# LM25148_eval_BRD.net
KiCad netlist of a schematic drawn in Altium Designer
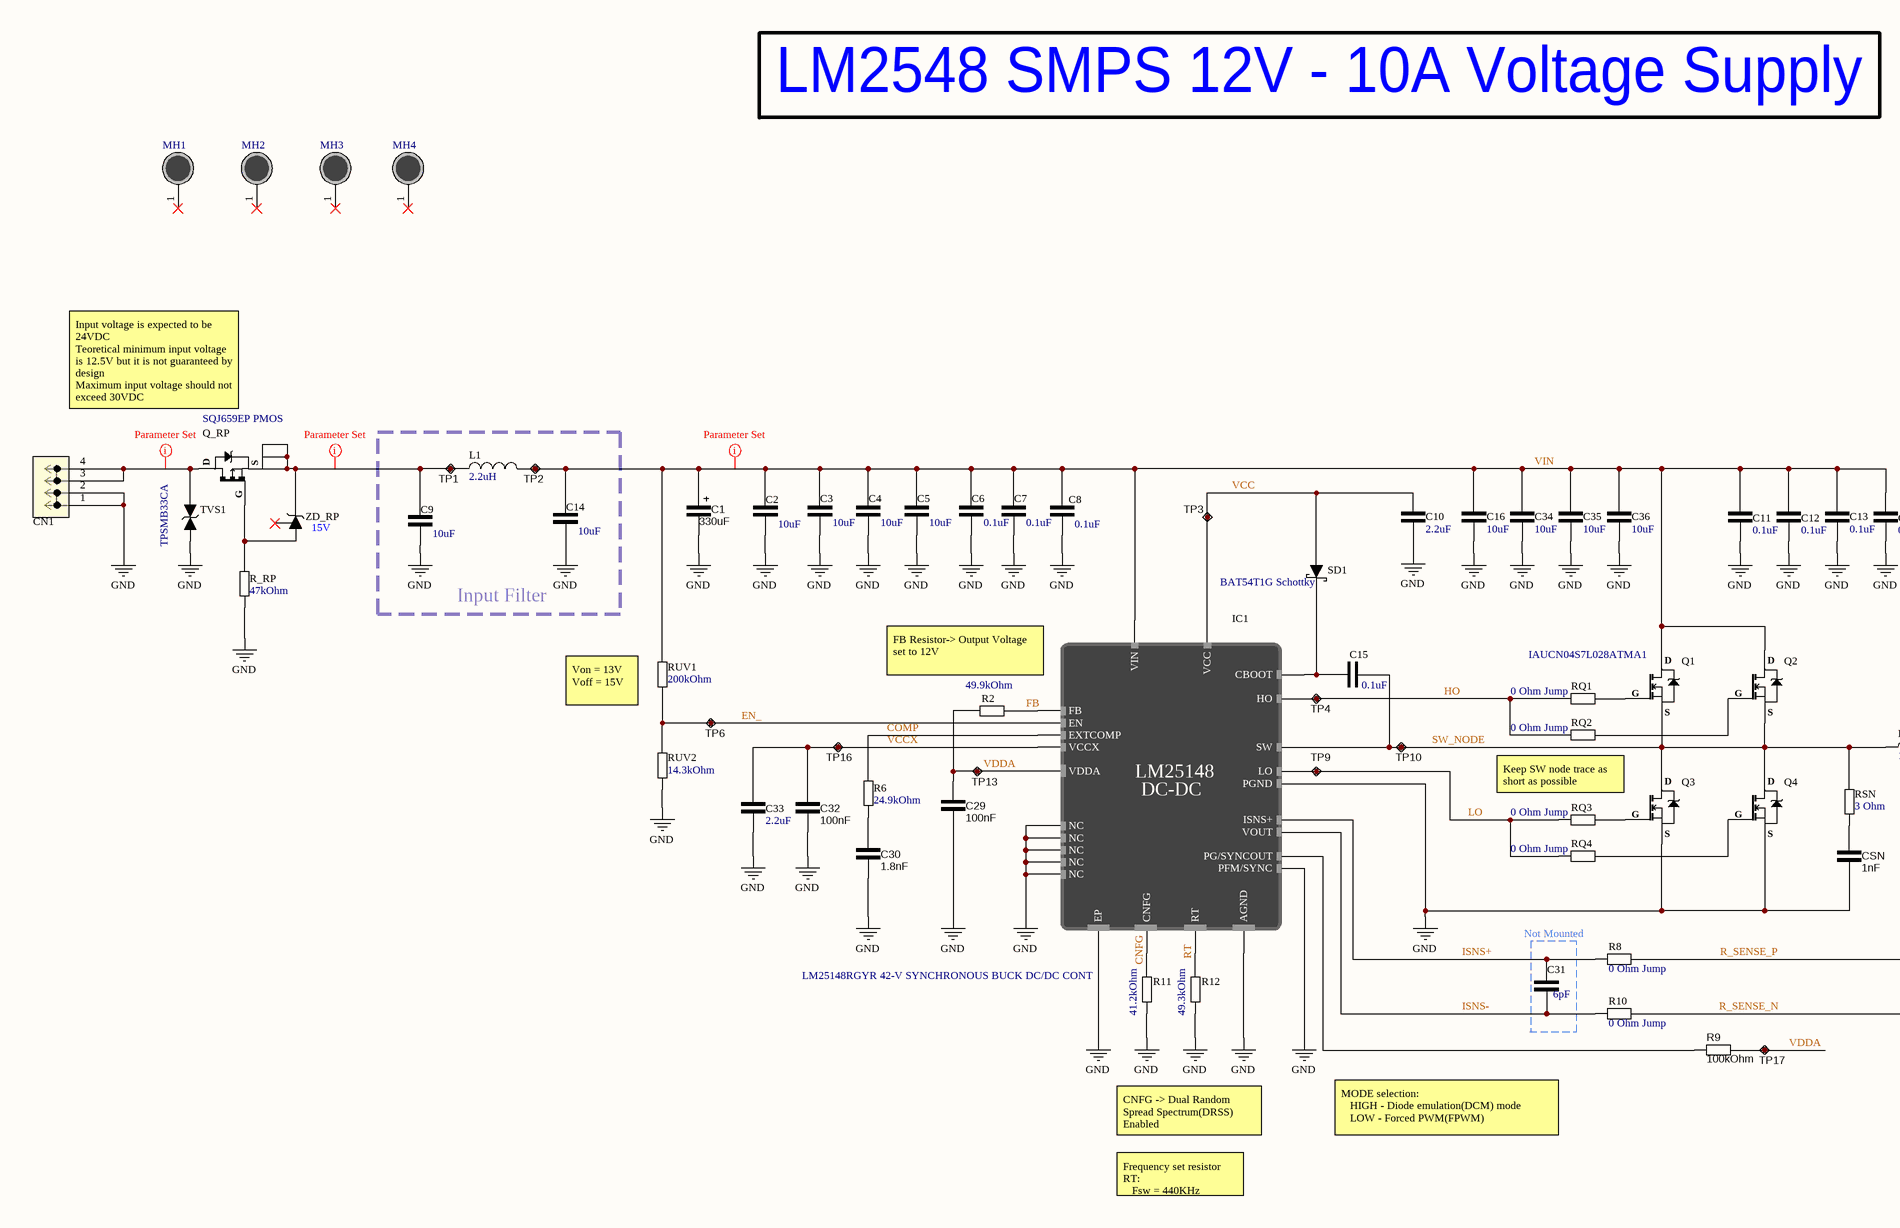
[diagram p0: LM25148_eval_BRD.SchDoc, left]
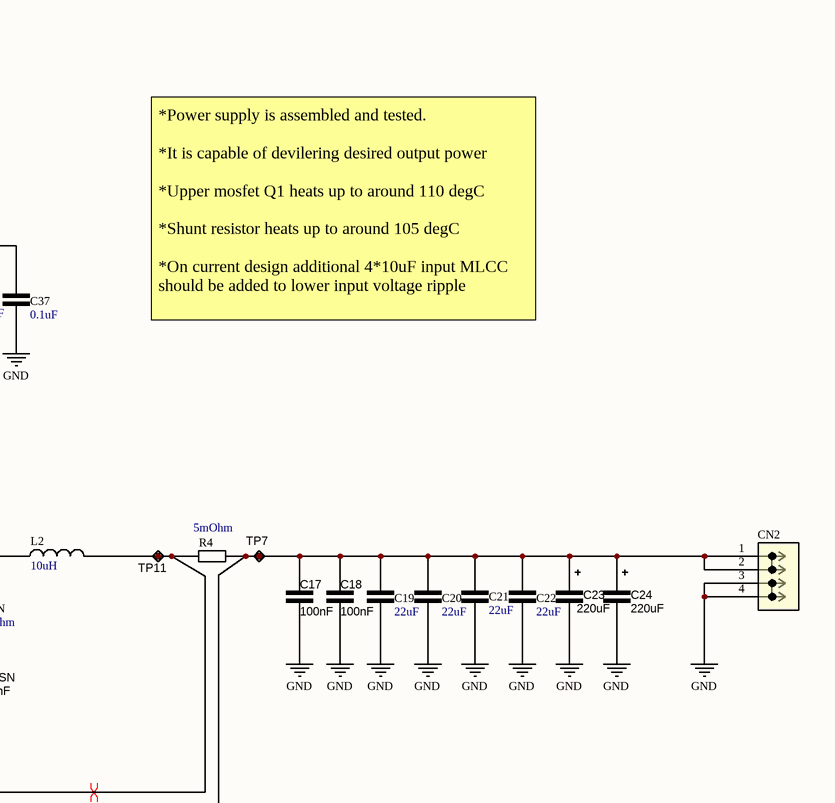
[diagram p1: LM25148_eval_BRD.SchDoc, right]

(export (version "E")
  (design (tool "Eeschema 10.0.6"))
  (components
    (comp (ref "C1")
      (value "330uF")
      (footprint "CAPAE109103X103M")
      (description "330 µF 50 V Aluminum Electrolytic Capacitors Radial, Can - SMD 120mOhm @ 100kHz 2000 Hrs @ 105°C")
      (fields (field (name "DIGIKEY PART NUMBER") "565-EMZR500ARA331MJA0GCT-ND"))
      (libsource (lib "CapacitorsIntegrated") (part "C000026"))
    )
    (comp (ref "C2")
      (value "10uF")
      (footprint "CAP_1206")
      (description "10 µF ±10% 50V Ceramic Capacitor X7R 1206 (3216 Metric)")
      (fields (field (name "DIGIKEY PART NUMBER") "1276-6767-1-ND"))
      (libsource (lib "CapacitorsIntegrated") (part "C000017"))
    )
    (comp (ref "C3")
      (value "10uF")
      (footprint "CAP_1206")
      (description "10 µF ±10% 50V Ceramic Capacitor X7R 1206 (3216 Metric)")
      (fields (field (name "DIGIKEY PART NUMBER") "1276-6767-1-ND"))
      (libsource (lib "") (part "C000017_1"))
    )
    (comp (ref "C4")
      (value "10uF")
      (footprint "CAP_1206")
      (description "10 µF ±10% 50V Ceramic Capacitor X7R 1206 (3216 Metric)")
      (fields (field (name "DIGIKEY PART NUMBER") "1276-6767-1-ND"))
      (libsource (lib "") (part "C000017_1"))
    )
    (comp (ref "C5")
      (value "10uF")
      (footprint "CAP_1206")
      (description "10 µF ±10% 50V Ceramic Capacitor X7R 1206 (3216 Metric)")
      (fields (field (name "DIGIKEY PART NUMBER") "1276-6767-1-ND"))
      (libsource (lib "") (part "C000017_1"))
    )
    (comp (ref "C6")
      (value "0.1uF")
      (footprint "CAP_0603")
      (description "0.1 µF ±10% 50V Ceramic Capacitor X7R 0603 (1608 Metric)")
      (fields (field (name "DIGIKEY PART NUMBER") "1276-1000-1-ND"))
      (libsource (lib "") (part "C000018_1"))
    )
    (comp (ref "C7")
      (value "0.1uF")
      (footprint "CAP_0603")
      (description "0.1 µF ±10% 50V Ceramic Capacitor X7R 0603 (1608 Metric)")
      (fields (field (name "DIGIKEY PART NUMBER") "1276-1000-1-ND"))
      (libsource (lib "") (part "C000018_1"))
    )
    (comp (ref "C8")
      (value "0.1uF")
      (footprint "CAP_0603")
      (description "0.1 µF ±10% 50V Ceramic Capacitor X7R 0603 (1608 Metric)")
      (fields (field (name "DIGIKEY PART NUMBER") "1276-1000-1-ND"))
      (libsource (lib "CapacitorsIntegrated") (part "C000018"))
    )
    (comp (ref "C9")
      (value "10uF")
      (footprint "CAP_1206")
      (description "10 µF ±10% 50V Ceramic Capacitor X7R 1206 (3216 Metric)")
      (fields (field (name "DIGIKEY PART NUMBER") "1276-6767-1-ND"))
      (libsource (lib "CapacitorsIntegrated") (part "C000017"))
    )
    (comp (ref "C10")
      (value "2.2uF")
      (footprint "CAP_0603")
      (description "8 pF ±0.05pF 25V Ceramic Capacitor C0G, NP0 01005 (0402 Metric)")
      (fields (field (name "DIGIKEY PART NUMBER") "490-12731-1-ND"))
      (libsource (lib "") (part "C000014_1"))
    )
    (comp (ref "C11")
      (value "0.1uF")
      (footprint "CAP_0603")
      (description "0.1 µF ±10% 50V Ceramic Capacitor X7R 0603 (1608 Metric)")
      (fields (field (name "DIGIKEY PART NUMBER") "1276-1000-1-ND"))
      (libsource (lib "CapacitorsIntegrated") (part "C000018"))
    )
    (comp (ref "C12")
      (value "0.1uF")
      (footprint "CAP_0603")
      (description "0.1 µF ±10% 50V Ceramic Capacitor X7R 0603 (1608 Metric)")
      (fields (field (name "DIGIKEY PART NUMBER") "1276-1000-1-ND"))
      (libsource (lib "CapacitorsIntegrated") (part "C000018"))
    )
    (comp (ref "C13")
      (value "0.1uF")
      (footprint "CAP_0603")
      (description "0.1 µF ±10% 50V Ceramic Capacitor X7R 0603 (1608 Metric)")
      (fields (field (name "DIGIKEY PART NUMBER") "1276-1000-1-ND"))
      (libsource (lib "") (part "C000018_1"))
    )
    (comp (ref "C14")
      (value "10uF")
      (footprint "CAP_1206")
      (description "10 µF ±10% 50V Ceramic Capacitor X7R 1206 (3216 Metric)")
      (fields (field (name "DIGIKEY PART NUMBER") "1276-6767-1-ND"))
      (libsource (lib "CapacitorsIntegrated") (part "C000017"))
    )
    (comp (ref "C15")
      (value "0.1uF")
      (footprint "CAP_0603")
      (description "0.1 µF ±10% 50V Ceramic Capacitor X7R 0603 (1608 Metric)")
      (fields (field (name "DIGIKEY PART NUMBER") "1276-1000-1-ND"))
      (libsource (lib "") (part "C000018_2"))
    )
    (comp (ref "C16")
      (value "10uF")
      (footprint "CAP_1206")
      (description "10 µF ±10% 50V Ceramic Capacitor X7R 1206 (3216 Metric)")
      (fields (field (name "DIGIKEY PART NUMBER") "1276-6767-1-ND"))
      (libsource (lib "") (part "C000017_1"))
    )
    (comp (ref "C17")
      (value "100nF")
      (footprint "CAP_0603")
      (description "0.1 µF ±10% 25V Ceramic Capacitor X7R 0603 (1608 Metric)")
      (fields (field (name "DIGIKEY PART NUMBER") "478-KAM15AR71E104KTCT-ND"))
      (libsource (lib "CapacitorsIntegrated") (part "C000007"))
    )
    (comp (ref "C18")
      (value "100nF")
      (footprint "CAP_0603")
      (description "0.1 µF ±10% 25V Ceramic Capacitor X7R 0603 (1608 Metric)")
      (fields (field (name "DIGIKEY PART NUMBER") "478-KAM15AR71E104KTCT-ND"))
      (libsource (lib "CapacitorsIntegrated") (part "C000007"))
    )
    (comp (ref "C19")
      (value "22uF")
      (footprint "CAP_1210")
      (description "22 µF ±10% 25V Ceramic Capacitor X7R 1210 (3225 Metric)")
      (fields (field (name "DIGIKEY PART NUMBER") "1276-3392-1-ND"))
      (libsource (lib "") (part "C000032_1"))
    )
    (comp (ref "C20")
      (value "22uF")
      (footprint "CAP_1210")
      (description "22 µF ±10% 25V Ceramic Capacitor X7R 1210 (3225 Metric)")
      (fields (field (name "DIGIKEY PART NUMBER") "1276-3392-1-ND"))
      (libsource (lib "") (part "C000032_1"))
    )
    (comp (ref "C21")
      (value "22uF")
      (footprint "CAP_1210")
      (description "22 µF ±10% 25V Ceramic Capacitor X7R 1210 (3225 Metric)")
      (fields (field (name "DIGIKEY PART NUMBER") "1276-3392-1-ND"))
      (libsource (lib "CapacitorsIntegrated") (part "C000032"))
    )
    (comp (ref "C22")
      (value "22uF")
      (footprint "CAP_1210")
      (description "22 µF ±10% 25V Ceramic Capacitor X7R 1210 (3225 Metric)")
      (fields (field (name "DIGIKEY PART NUMBER") "1276-3392-1-ND"))
      (libsource (lib "") (part "C000032_1"))
    )
    (comp (ref "C23")
      (value "220uF")
      (footprint "CAPAE109103X103M")
      (description "220 µF 35 V Aluminum - Polymer Capacitors Radial, Can - SMD 23mOhm 1000 Hrs @ 150°C")
      (fields (field (name "DIGIKEY PART NUMBER") "399-A785MN227M1VLAS023CT-ND"))
      (libsource (lib "CapacitorsIntegrated") (part "C000033"))
    )
    (comp (ref "C24")
      (value "220uF")
      (footprint "CAPAE109103X103M")
      (description "220 µF 35 V Aluminum - Polymer Capacitors Radial, Can - SMD 23mOhm 1000 Hrs @ 150°C")
      (fields (field (name "DIGIKEY PART NUMBER") "399-A785MN227M1VLAS023CT-ND"))
      (libsource (lib "CapacitorsIntegrated") (part "C000033"))
    )
    (comp (ref "C29")
      (value "100nF")
      (footprint "CAP_0603")
      (description "0.1 µF ±10% 25V Ceramic Capacitor X7R 0603 (1608 Metric)")
      (fields (field (name "DIGIKEY PART NUMBER") "478-KAM15AR71E104KTCT-ND"))
      (libsource (lib "CapacitorsIntegrated") (part "C000007"))
    )
    (comp (ref "C30")
      (value "1.8nF")
      (footprint "CAP_0603")
      (description "1800 pF ±10% 25V Ceramic Capacitor X7R 0603 (1608 Metric)")
      (fields (field (name "DIGIKEY PART NUMBER") "399-15370-1-ND"))
      (libsource (lib "CapacitorsIntegrated") (part "C000027"))
    )
    (comp (ref "C31")
      (value "6pF")
      (footprint "CAP_0402")
      (description "6 pF ±0.5pF 25V Ceramic Capacitor C0G, NP0 0402 (1005 Metric)")
      (fields (field (name "DIGIKEY PART NUMBER") "399-CBR04C609D3GACCT-ND"))
      (libsource (lib "CapacitorsIntegrated") (part "C000016"))
    )
    (comp (ref "C32")
      (value "100nF")
      (footprint "CAP_0603")
      (description "0.1 µF ±10% 25V Ceramic Capacitor X7R 0603 (1608 Metric)")
      (fields (field (name "DIGIKEY PART NUMBER") "478-KAM15AR71E104KTCT-ND"))
      (libsource (lib "CapacitorsIntegrated") (part "C000007"))
    )
    (comp (ref "C33")
      (value "2.2uF")
      (footprint "CAP_0603")
      (description "8 pF ±0.05pF 25V Ceramic Capacitor C0G, NP0 01005 (0402 Metric)")
      (fields (field (name "DIGIKEY PART NUMBER") "490-12731-1-ND"))
      (libsource (lib "CapacitorsIntegrated") (part "C000014"))
    )
    (comp (ref "C34")
      (value "10uF")
      (footprint "CAP_1206")
      (description "10 µF ±10% 50V Ceramic Capacitor X7R 1206 (3216 Metric)")
      (fields (field (name "DIGIKEY PART NUMBER") "1276-6767-1-ND"))
      (libsource (lib "") (part "C000017_1"))
    )
    (comp (ref "C35")
      (value "10uF")
      (footprint "CAP_1206")
      (description "10 µF ±10% 50V Ceramic Capacitor X7R 1206 (3216 Metric)")
      (fields (field (name "DIGIKEY PART NUMBER") "1276-6767-1-ND"))
      (libsource (lib "") (part "C000017_1"))
    )
    (comp (ref "C36")
      (value "10uF")
      (footprint "CAP_1206")
      (description "10 µF ±10% 50V Ceramic Capacitor X7R 1206 (3216 Metric)")
      (fields (field (name "DIGIKEY PART NUMBER") "1276-6767-1-ND"))
      (libsource (lib "") (part "C000017_1"))
    )
    (comp (ref "C37")
      (value "0.1uF")
      (footprint "CAP_0603")
      (description "0.1 µF ±10% 50V Ceramic Capacitor X7R 0603 (1608 Metric)")
      (fields (field (name "DIGIKEY PART NUMBER") "1276-1000-1-ND"))
      (libsource (lib "CapacitorsIntegrated") (part "C000018"))
    )
    (comp (ref "CN1")
      (value "TERM BLK PCB LEVER 3.5MM 2POS")
      (footprint "CONN2_2601-1102_WAG")
      (description "2 Position Wire to Board Terminal Block Horizontal with Board 0.138\" (3.50mm) Through Hole")
      (fields (field (name "DIGIKEY PART NUMBER") "2946-2601-1102-ND"))
      (libsource (lib "") (part "00000017_1"))
    )
    (comp (ref "CN2")
      (value "TERM BLK PCB LEVER 3.5MM 2POS")
      (footprint "CONN2_2601-1102_WAG")
      (description "2 Position Wire to Board Terminal Block Horizontal with Board 0.138\" (3.50mm) Through Hole")
      (fields (field (name "DIGIKEY PART NUMBER") "2946-2601-1102-ND"))
      (libsource (lib "ElectroMechanical") (part "00000017"))
    )
    (comp (ref "CSN")
      (value "1nF")
      (footprint "CAP_0805")
      (description "1000 pF ±10% 100V Ceramic Capacitor X7R 0805 (2012 Metric)")
      (fields (field (name "DIGIKEY PART NUMBER") "311-1472-1-ND"))
      (libsource (lib "CapacitorsIntegrated") (part "C000035"))
    )
    (comp (ref "IC1")
      (value "LM25148RGYR 42-V SYNCHRONOUS BUCK DC/DC CONT")
      (footprint "VQFN25_RGY_TEX")
      (description "Buck Regulator Positive Output Step-Down DC-DC Controller IC 24-VQFN (5.5x3.5)")
      (fields
        (field (name "DIGIKEY PART NUMBER") "296-LM25148RGYRCT-ND")
        (field (name "MOUSER PART NUMBER") "595-LM25148RGYR")
      )
      (libsource (lib "IntegratedCircuits") (part "LM25148RGYR"))
    )
    (comp (ref "L1")
      (value "2.2uH")
      (footprint "IHLP-3232DZ-51")
      (description "FIXED IND 2.2UH 11.5A 12.5 MOHM")
      (fields
        (field (name "DIGIKEY PART NUMBER") "541-IHLP3232DZER2R2M5ACT-ND")
        (field (name "MOUSER PART NUMBER") "70-IHLP3232DZR2R2M5A")
      )
      (libsource (lib "InductorIntegrated") (part "L000015"))
    )
    (comp (ref "L2")
      (value "10uH")
      (footprint "INDP135126X65N")
      (description "FIXED IND 10UH 11A 15.8 MOHM SMD")
      (fields
        (field (name "DIGIKEY PART NUMBER") "553-4029-1-ND")
        (field (name "MOUSER PART NUMBER") "673-PA4343.103ANLT")
      )
      (libsource (lib "InductorIntegrated") (part "L000016"))
    )
    (comp (ref "MH1")
      (value "Mounting Hole")
      (footprint "HOLE-3mm")
      (description "Mounting Hole 3mm")
      (libsource (lib "ElectroMechanical") (part "00000006"))
    )
    (comp (ref "MH2")
      (value "Mounting Hole")
      (footprint "HOLE-3mm")
      (description "Mounting Hole 3mm")
      (libsource (lib "ElectroMechanical") (part "00000006"))
    )
    (comp (ref "MH3")
      (value "Mounting Hole")
      (footprint "HOLE-3mm")
      (description "Mounting Hole 3mm")
      (libsource (lib "ElectroMechanical") (part "00000006"))
    )
    (comp (ref "MH4")
      (value "Mounting Hole")
      (footprint "HOLE-3mm")
      (description "Mounting Hole 3mm")
      (libsource (lib "ElectroMechanical") (part "00000006"))
    )
    (comp (ref "Q1")
      (value "IAUCN04S7L028ATMA1")
      (footprint "PG-TDSON-8-33")
      (description "N-Channel 40 V 100A Surface Mount PG-TDSON-8-33")
      (fields
        (field (name "DIGIKEY PART NUMBER") "448-IAUCN04S7L028ATMA1CT-ND")
        (field (name "MOUSER PART NUMBER") "726-IAUCN04S7L028ATM")
      )
      (libsource (lib "Miscellaneous_Lib1") (part "00000014"))
    )
    (comp (ref "Q2")
      (value "IAUCN04S7L028ATMA1")
      (footprint "PG-TDSON-8-33")
      (description "N-Channel 40 V 100A Surface Mount PG-TDSON-8-33")
      (fields
        (field (name "DIGIKEY PART NUMBER") "448-IAUCN04S7L028ATMA1CT-ND")
        (field (name "MOUSER PART NUMBER") "726-IAUCN04S7L028ATM")
      )
      (libsource (lib "Miscellaneous_Lib1") (part "00000014"))
    )
    (comp (ref "Q3")
      (value "IAUCN04S7L028ATMA1")
      (footprint "PG-TDSON-8-33")
      (description "N-Channel 40 V 100A Surface Mount PG-TDSON-8-33")
      (fields
        (field (name "DIGIKEY PART NUMBER") "448-IAUCN04S7L028ATMA1CT-ND")
        (field (name "MOUSER PART NUMBER") "726-IAUCN04S7L028ATM")
      )
      (libsource (lib "Miscellaneous_Lib1") (part "00000014"))
    )
    (comp (ref "Q4")
      (value "IAUCN04S7L028ATMA1")
      (footprint "PG-TDSON-8-33")
      (description "N-Channel 40 V 100A Surface Mount PG-TDSON-8-33")
      (fields
        (field (name "DIGIKEY PART NUMBER") "448-IAUCN04S7L028ATMA1CT-ND")
        (field (name "MOUSER PART NUMBER") "726-IAUCN04S7L028ATM")
      )
      (libsource (lib "Miscellaneous_Lib1") (part "00000014"))
    )
    (comp (ref "Q_RP")
      (value "SQJ659EP PMOS")
      (footprint "PowerPAK SO-8L SINGLE")
      (description "P-Channel 60 V 52A (Tc) 83W (Tc) Surface Mount PowerPAK® SO-8")
      (fields
        (field (name "DIGIKEY PART NUMBER") "SQJ459EP-T1_GE3CT-ND")
        (field (name "MOUSER PART NUMBER") "78-SQJ459EP-T2_BE3")
      )
      (libsource (lib "Miscellaneous_Lib1") (part "00000005"))
    )
    (comp (ref "R2")
      (value "49.9kOhm")
      (footprint "RES_0603")
      (description "49.9 kOhms ±1% 0.1W, 1/10W Chip Resistor 0603 (1608 Metric) Moisture Resistant Thick Film")
      (fields (field (name "DIGIKEY PART NUMBER") "541-49.9KHCT-ND"))
      (libsource (lib "ResistorsIntegrated") (part "R000025"))
    )
    (comp (ref "R4")
      (value "5mOhm")
      (footprint "SENSE_RES_2512")
      (fields (field (name "DIGIKEY PART NUMBER") "CRF2512-FZ-R005ELFCT-ND"))
      (libsource (lib "ResistorsIntegrated") (part "R000033"))
    )
    (comp (ref "R6")
      (value "24.9kOhm")
      (footprint "RES_0603")
      (description "24.9 kOhms ±1% 0.1W, 1/10W Chip Resistor 0603 (1608 Metric) Automotive AEC-Q200 Thick Film")
      (fields (field (name "DIGIKEY PART NUMBER") "P24.9KHCT-ND"))
      (libsource (lib "ResistorsIntegrated") (part "R000017"))
    )
    (comp (ref "R8")
      (value "0 Ohm Jump")
      (footprint "RES_0402")
      (description "0 Ohms Jumper Chip Resistor 0402 (1005 Metric) Automotive AEC-Q200 Thick Film")
      (fields (field (name "DIGIKEY PART NUMBER") "P0.0JCT-ND"))
      (libsource (lib "ResistorsIntegrated") (part "R000008"))
    )
    (comp (ref "R9")
      (value "100kOhm")
      (footprint "RES_0603")
      (description "100 kOhms ±1% 0.1W, 1/10W Chip Resistor 0603 (1608 Metric) Automotive AEC-Q200 Thick Film")
      (fields (field (name "DIGIKEY PART NUMBER") "RMCF0603FG100KCT-ND"))
      (libsource (lib "ResistorsIntegrated") (part "R000006"))
    )
    (comp (ref "R10")
      (value "0 Ohm Jump")
      (footprint "RES_0402")
      (description "0 Ohms Jumper Chip Resistor 0402 (1005 Metric) Automotive AEC-Q200 Thick Film")
      (fields (field (name "DIGIKEY PART NUMBER") "P0.0JCT-ND"))
      (libsource (lib "ResistorsIntegrated") (part "R000008"))
    )
    (comp (ref "R11")
      (value "41.2kOhm")
      (footprint "RES_0603")
      (description "41.2 kOhms ±1% 0.1W, 1/10W Chip Resistor 0603 (1608 Metric) Automotive AEC-Q200 Thick Film")
      (fields (field (name "DIGIKEY PART NUMBER") "P41.2KHCT-ND"))
      (libsource (lib "ResistorsIntegrated") (part "R000015"))
    )
    (comp (ref "R12")
      (value "49.3kOhm")
      (footprint "RES_0603")
      (description "49.3 kOhms ±0.1% 0.1W, 1/10W Chip Resistor 0603 (1608 Metric) Thin Film")
      (fields (field (name "DIGIKEY PART NUMBER") "13-RT0603BRD0749K3LCT-ND"))
      (libsource (lib "ResistorsIntegrated") (part "R000023"))
    )
    (comp (ref "RQ1")
      (value "0 Ohm Jump")
      (footprint "RES_0402")
      (description "0 Ohms Jumper Chip Resistor 0402 (1005 Metric) Automotive AEC-Q200 Thick Film")
      (fields (field (name "DIGIKEY PART NUMBER") "P0.0JCT-ND"))
      (libsource (lib "ResistorsIntegrated") (part "R000008"))
    )
    (comp (ref "RQ2")
      (value "0 Ohm Jump")
      (footprint "RES_0402")
      (description "0 Ohms Jumper Chip Resistor 0402 (1005 Metric) Automotive AEC-Q200 Thick Film")
      (fields (field (name "DIGIKEY PART NUMBER") "P0.0JCT-ND"))
      (libsource (lib "ResistorsIntegrated") (part "R000008"))
    )
    (comp (ref "RQ3")
      (value "0 Ohm Jump")
      (footprint "RES_0402")
      (description "0 Ohms Jumper Chip Resistor 0402 (1005 Metric) Automotive AEC-Q200 Thick Film")
      (fields (field (name "DIGIKEY PART NUMBER") "P0.0JCT-ND"))
      (libsource (lib "ResistorsIntegrated") (part "R000008"))
    )
    (comp (ref "RQ4")
      (value "0 Ohm Jump")
      (footprint "RES_0402")
      (description "0 Ohms Jumper Chip Resistor 0402 (1005 Metric) Automotive AEC-Q200 Thick Film")
      (fields (field (name "DIGIKEY PART NUMBER") "P0.0JCT-ND"))
      (libsource (lib "ResistorsIntegrated") (part "R000008"))
    )
    (comp (ref "RSN")
      (value "3 Ohm")
      (footprint "RES_0805")
      (description "3 Ohms ±1% 0.125W, 1/8W Chip Resistor 0805 (2012 Metric) Moisture Resistant Thick Film")
      (fields (field (name "DIGIKEY PART NUMBER") "311-3.00CRCT-ND"))
      (libsource (lib "ResistorsIntegrated") (part "R000034"))
    )
    (comp (ref "RUV1")
      (value "200kOhm")
      (footprint "RES_0603")
      (description "200 kOhms ±1% 0.1W, 1/10W Chip Resistor 0603 (1608 Metric) Moisture Resistant Thick Film")
      (fields (field (name "DIGIKEY PART NUMBER") "311-200KHRCT-ND"))
      (libsource (lib "ResistorsIntegrated") (part "R000031"))
    )
    (comp (ref "RUV2")
      (value "14.3kOhm")
      (footprint "RES_0603")
      (description "14.3 kOhms ±1% 0.1W, 1/10W Chip Resistor 0603 (1608 Metric) Automotive AEC-Q200 Thick Film")
      (fields (field (name "DIGIKEY PART NUMBER") "RMCF0603FT14K3CT-ND"))
      (libsource (lib "ResistorsIntegrated") (part "R000032"))
    )
    (comp (ref "R_RP")
      (value "47kOhm")
      (footprint "RES_0603")
      (description "47 kOhms ±1% 0.1W, 1/10W Chip Resistor 0603 (1608 Metric) Moisture Resistant Thick Film")
      (fields (field (name "DIGIKEY PART NUMBER") "311-47.0KHRCT-ND"))
      (libsource (lib "ResistorsIntegrated") (part "R000010"))
    )
    (comp (ref "SD1")
      (value "BAT54T1G Schottky")
      (footprint "SODFL371X135-2N")
      (description "Diode 30 V 200mA Surface Mount SOD-123")
      (fields (field (name "DIGIKEY PART NUMBER") "BAT54T1GOSCT-ND"))
      (libsource (lib "Miscellaneous_Lib1") (part "00000009"))
    )
    (comp (ref "TP1")
      (value "Test point")
      (footprint "TestPoint")
      (description "Test point 1mm")
      (libsource (lib "IntegratedCircuits") (part "TP002"))
    )
    (comp (ref "TP2")
      (value "Test point")
      (footprint "TestPoint")
      (description "Test point 1mm")
      (libsource (lib "IntegratedCircuits") (part "TP002"))
    )
    (comp (ref "TP3")
      (value "Test point")
      (footprint "TestPoint")
      (description "Test point 1mm")
      (libsource (lib "IntegratedCircuits") (part "TP002"))
    )
    (comp (ref "TP4")
      (value "Test point")
      (footprint "TestPoint")
      (description "Test point 1mm")
      (libsource (lib "IntegratedCircuits") (part "TP002"))
    )
    (comp (ref "TP6")
      (value "Test point")
      (footprint "TestPoint")
      (description "Test point 1mm")
      (libsource (lib "IntegratedCircuits") (part "TP002"))
    )
    (comp (ref "TP7")
      (value "Test point")
      (footprint "TestPoint")
      (description "Test point 1mm")
      (libsource (lib "IntegratedCircuits") (part "TP002"))
    )
    (comp (ref "TP9")
      (value "Test point")
      (footprint "TestPoint")
      (description "Test point 1mm")
      (libsource (lib "IntegratedCircuits") (part "TP002"))
    )
    (comp (ref "TP10")
      (value "Test point")
      (footprint "TestPoint")
      (description "Test point 1mm")
      (libsource (lib "IntegratedCircuits") (part "TP002"))
    )
    (comp (ref "TP11")
      (value "Test point")
      (footprint "TestPoint")
      (description "Test point 1mm")
      (libsource (lib "IntegratedCircuits") (part "TP002"))
    )
    (comp (ref "TP13")
      (value "Test point")
      (footprint "TestPoint")
      (description "Test point 1mm")
      (libsource (lib "IntegratedCircuits") (part "TP002"))
    )
    (comp (ref "TP16")
      (value "Test point")
      (footprint "TestPoint")
      (description "Test point 1mm")
      (libsource (lib "IntegratedCircuits") (part "TP002"))
    )
    (comp (ref "TP17")
      (value "Test point")
      (footprint "TestPoint")
      (description "Test point 1mm")
      (libsource (lib "IntegratedCircuits") (part "TP002"))
    )
    (comp (ref "TVS1")
      (value "TPSMB33CA")
      (footprint "DO-214AA")
      (description "45.7V Clamp 13.3A Ipp Tvs Diode Surface Mount DO-214AA (SMBJ)")
      (fields (field (name "DIGIKEY PART NUMBER") "F6323CT-ND"))
      (libsource (lib "Miscellaneous_Lib1") (part "00000015"))
    )
    (comp (ref "ZD_RP")
      (value "DZ23C15-E3-08 Zener Diode")
      (footprint "SOT95P245X96-3N")
      (description "Zener Diode Array 1 Pair Common Cathode 15 V 300 mW ±5% SOT-23-3")
      (fields (field (name "DIGIKEY PART NUMBER") "112-DZ23C15-E3-08CT-ND"))
      (libsource (lib "Miscellaneous_Lib1") (part "00000006"))
    )
  )
  (nets
    (net (code "1") (name "/CNFG") (class "Default")
      (node (ref "IC1") (pin "3") (pinfunction "CNFG_3") (pintype "passive"))
      (node (ref "R11") (pin "2") (pinfunction "2_2") (pintype "passive"))
    )
    (net (code "2") (name "/COMP") (class "Default")
      (node (ref "IC1") (pin "5") (pinfunction "EXTCOMP_5") (pintype "passive"))
      (node (ref "R6") (pin "2") (pinfunction "2_2") (pintype "passive"))
    )
    (net (code "3") (name "/EN_") (class "Default")
      (node (ref "IC1") (pin "19") (pinfunction "EN_19") (pintype "passive"))
      (node (ref "RUV1") (pin "1") (pinfunction "1_1") (pintype "passive"))
      (node (ref "RUV2") (pin "2") (pinfunction "2_2") (pintype "passive"))
      (node (ref "TP6") (pin "1") (pinfunction "1_1") (pintype "passive"))
    )
    (net (code "4") (name "/FB") (class "Default")
      (node (ref "IC1") (pin "6") (pinfunction "FB_6") (pintype "passive"))
      (node (ref "R2") (pin "2") (pinfunction "2_2") (pintype "passive"))
    )
    (net (code "5") (name "/HO") (class "Default")
      (node (ref "IC1") (pin "13") (pinfunction "HO_13") (pintype "passive"))
      (node (ref "RQ1") (pin "1") (pinfunction "1_1") (pintype "passive"))
      (node (ref "RQ2") (pin "1") (pinfunction "1_1") (pintype "passive"))
      (node (ref "TP4") (pin "1") (pinfunction "1_1") (pintype "passive"))
    )
    (net (code "6") (name "/ISNS+") (class "Default")
      (node (ref "C31") (pin "2") (pinfunction "2_2") (pintype "passive"))
      (node (ref "IC1") (pin "20") (pinfunction "ISNS+_20") (pintype "passive"))
      (node (ref "R8") (pin "1") (pinfunction "1_1") (pintype "passive"))
    )
    (net (code "7") (name "/ISNS-") (class "Default")
      (node (ref "C31") (pin "1") (pinfunction "1_1") (pintype "passive"))
      (node (ref "IC1") (pin "21") (pinfunction "VOUT_21") (pintype "passive"))
      (node (ref "R10") (pin "1") (pinfunction "1_1") (pintype "passive"))
    )
    (net (code "8") (name "/LO") (class "Default")
      (node (ref "IC1") (pin "11") (pinfunction "LO_11") (pintype "passive"))
      (node (ref "RQ3") (pin "1") (pinfunction "1_1") (pintype "passive"))
      (node (ref "RQ4") (pin "1") (pinfunction "1_1") (pintype "passive"))
      (node (ref "TP9") (pin "1") (pinfunction "1_1") (pintype "passive"))
    )
    (net (code "9") (name "/RT") (class "Default")
      (node (ref "IC1") (pin "4") (pinfunction "RT_4") (pintype "passive"))
      (node (ref "R12") (pin "2") (pinfunction "2_2") (pintype "passive"))
    )
    (net (code "10") (name "/R_SENSE_N") (class "Default")
      (node (ref "C17") (pin "2") (pinfunction "2_2") (pintype "passive"))
      (node (ref "C18") (pin "2") (pinfunction "2_2") (pintype "passive"))
      (node (ref "C19") (pin "1") (pinfunction "1_1") (pintype "passive"))
      (node (ref "C20") (pin "1") (pinfunction "1_1") (pintype "passive"))
      (node (ref "C21") (pin "2") (pinfunction "2_2") (pintype "passive"))
      (node (ref "C22") (pin "1") (pinfunction "1_1") (pintype "passive"))
      (node (ref "C23") (pin "1") (pinfunction "1_1") (pintype "passive"))
      (node (ref "C24") (pin "1") (pinfunction "1_1") (pintype "passive"))
      (node (ref "CN2") (pin "1") (pinfunction "1_1_1") (pintype "passive"))
      (node (ref "CN2") (pin "2") (pinfunction "1_2_2") (pintype "passive"))
      (node (ref "R10") (pin "2") (pinfunction "2_2") (pintype "passive"))
      (node (ref "R4") (pin "2") (pinfunction "2_2") (pintype "passive"))
      (node (ref "TP7") (pin "1") (pinfunction "1_1") (pintype "passive"))
    )
    (net (code "11") (name "/R_SENSE_P") (class "Default")
      (node (ref "L2") (pin "2") (pinfunction "2_2") (pintype "passive"))
      (node (ref "R4") (pin "1") (pinfunction "1_1") (pintype "passive"))
      (node (ref "R8") (pin "2") (pinfunction "2_2") (pintype "passive"))
      (node (ref "TP11") (pin "1") (pinfunction "1_1") (pintype "passive"))
    )
    (net (code "12") (name "/SW_NODE") (class "Default")
      (node (ref "C15") (pin "1") (pinfunction "1_1") (pintype "passive"))
      (node (ref "IC1") (pin "14") (pinfunction "SW_14") (pintype "passive"))
      (node (ref "L2") (pin "1") (pinfunction "1_1") (pintype "passive"))
      (node (ref "Q1") (pin "S") (pinfunction "Source_S") (pintype "passive"))
      (node (ref "Q2") (pin "S") (pinfunction "Source_S") (pintype "passive"))
      (node (ref "Q3") (pin "D") (pinfunction "Drain_D") (pintype "passive"))
      (node (ref "Q4") (pin "D") (pinfunction "Drain_D") (pintype "passive"))
      (node (ref "RSN") (pin "2") (pinfunction "2_2") (pintype "passive"))
      (node (ref "TP10") (pin "1") (pinfunction "1_1") (pintype "passive"))
    )
    (net (code "13") (name "/VCC") (class "Default")
      (node (ref "C10") (pin "2") (pinfunction "2_2") (pintype "passive"))
      (node (ref "IC1") (pin "9") (pinfunction "VCC_9") (pintype "passive"))
      (node (ref "SD1") (pin "1") (pinfunction "Anode_1") (pintype "passive"))
      (node (ref "TP3") (pin "1") (pinfunction "1_1") (pintype "passive"))
    )
    (net (code "14") (name "/VCCX") (class "Default")
      (node (ref "C32") (pin "2") (pinfunction "2_2") (pintype "passive"))
      (node (ref "C33") (pin "1") (pinfunction "1_1") (pintype "passive"))
      (node (ref "IC1") (pin "16") (pinfunction "VCCX_16") (pintype "passive"))
      (node (ref "TP16") (pin "1") (pinfunction "1_1") (pintype "passive"))
    )
    (net (code "15") (name "/VDDA") (class "Default")
      (node (ref "C29") (pin "2") (pinfunction "2_2") (pintype "passive"))
      (node (ref "IC1") (pin "8") (pinfunction "VDDA_8") (pintype "passive"))
      (node (ref "R2") (pin "1") (pinfunction "1_1") (pintype "passive"))
      (node (ref "R9") (pin "2") (pinfunction "2_2") (pintype "passive"))
      (node (ref "TP13") (pin "1") (pinfunction "1_1") (pintype "passive"))
      (node (ref "TP17") (pin "1") (pinfunction "1_1") (pintype "passive"))
    )
    (net (code "16") (name "/VIN") (class "Default")
      (node (ref "C1") (pin "1") (pinfunction "1_1") (pintype "passive"))
      (node (ref "C11") (pin "2") (pinfunction "2_2") (pintype "passive"))
      (node (ref "C12") (pin "2") (pinfunction "2_2") (pintype "passive"))
      (node (ref "C13") (pin "1") (pinfunction "1_1") (pintype "passive"))
      (node (ref "C14") (pin "2") (pinfunction "2_2") (pintype "passive"))
      (node (ref "C16") (pin "1") (pinfunction "1_1") (pintype "passive"))
      (node (ref "C2") (pin "2") (pinfunction "2_2") (pintype "passive"))
      (node (ref "C3") (pin "1") (pinfunction "1_1") (pintype "passive"))
      (node (ref "C34") (pin "1") (pinfunction "1_1") (pintype "passive"))
      (node (ref "C35") (pin "1") (pinfunction "1_1") (pintype "passive"))
      (node (ref "C36") (pin "1") (pinfunction "1_1") (pintype "passive"))
      (node (ref "C37") (pin "2") (pinfunction "2_2") (pintype "passive"))
      (node (ref "C4") (pin "1") (pinfunction "1_1") (pintype "passive"))
      (node (ref "C5") (pin "1") (pinfunction "1_1") (pintype "passive"))
      (node (ref "C6") (pin "1") (pinfunction "1_1") (pintype "passive"))
      (node (ref "C7") (pin "1") (pinfunction "1_1") (pintype "passive"))
      (node (ref "C8") (pin "2") (pinfunction "2_2") (pintype "passive"))
      (node (ref "IC1") (pin "12") (pinfunction "VIN_12") (pintype "passive"))
      (node (ref "L1") (pin "2") (pinfunction "2_2") (pintype "passive"))
      (node (ref "Q1") (pin "D") (pinfunction "Drain_D") (pintype "passive"))
      (node (ref "Q2") (pin "D") (pinfunction "Drain_D") (pintype "passive"))
      (node (ref "RUV1") (pin "2") (pinfunction "2_2") (pintype "passive"))
      (node (ref "TP2") (pin "1") (pinfunction "1_1") (pintype "passive"))
    )
    (net (code "17") (name "GND") (class "Default")
      (node (ref "C1") (pin "2") (pinfunction "2_2") (pintype "passive"))
      (node (ref "C10") (pin "1") (pinfunction "1_1") (pintype "passive"))
      (node (ref "C11") (pin "1") (pinfunction "1_1") (pintype "passive"))
      (node (ref "C12") (pin "1") (pinfunction "1_1") (pintype "passive"))
      (node (ref "C13") (pin "2") (pinfunction "2_2") (pintype "passive"))
      (node (ref "C14") (pin "1") (pinfunction "1_1") (pintype "passive"))
      (node (ref "C16") (pin "2") (pinfunction "2_2") (pintype "passive"))
      (node (ref "C17") (pin "1") (pinfunction "1_1") (pintype "passive"))
      (node (ref "C18") (pin "1") (pinfunction "1_1") (pintype "passive"))
      (node (ref "C19") (pin "2") (pinfunction "2_2") (pintype "passive"))
      (node (ref "C2") (pin "1") (pinfunction "1_1") (pintype "passive"))
      (node (ref "C20") (pin "2") (pinfunction "2_2") (pintype "passive"))
      (node (ref "C21") (pin "1") (pinfunction "1_1") (pintype "passive"))
      (node (ref "C22") (pin "2") (pinfunction "2_2") (pintype "passive"))
      (node (ref "C23") (pin "2") (pinfunction "2_2") (pintype "passive"))
      (node (ref "C24") (pin "2") (pinfunction "2_2") (pintype "passive"))
      (node (ref "C29") (pin "1") (pinfunction "1_1") (pintype "passive"))
      (node (ref "C3") (pin "2") (pinfunction "2_2") (pintype "passive"))
      (node (ref "C30") (pin "1") (pinfunction "1_1") (pintype "passive"))
      (node (ref "C32") (pin "1") (pinfunction "1_1") (pintype "passive"))
      (node (ref "C33") (pin "2") (pinfunction "2_2") (pintype "passive"))
      (node (ref "C34") (pin "2") (pinfunction "2_2") (pintype "passive"))
      (node (ref "C35") (pin "2") (pinfunction "2_2") (pintype "passive"))
      (node (ref "C36") (pin "2") (pinfunction "2_2") (pintype "passive"))
      (node (ref "C37") (pin "1") (pinfunction "1_1") (pintype "passive"))
      (node (ref "C4") (pin "2") (pinfunction "2_2") (pintype "passive"))
      (node (ref "C5") (pin "2") (pinfunction "2_2") (pintype "passive"))
      (node (ref "C6") (pin "2") (pinfunction "2_2") (pintype "passive"))
      (node (ref "C7") (pin "2") (pinfunction "2_2") (pintype "passive"))
      (node (ref "C8") (pin "1") (pinfunction "1_1") (pintype "passive"))
      (node (ref "C9") (pin "1") (pinfunction "1_1") (pintype "passive"))
      (node (ref "CN1") (pin "1") (pinfunction "1_1_1") (pintype "passive"))
      (node (ref "CN1") (pin "2") (pinfunction "1_2_2") (pintype "passive"))
      (node (ref "CN2") (pin "3") (pinfunction "2_1_3") (pintype "passive"))
      (node (ref "CN2") (pin "4") (pinfunction "2_2_4") (pintype "passive"))
      (node (ref "CSN") (pin "1") (pinfunction "1_1") (pintype "passive"))
      (node (ref "IC1") (pin "1") (pinfunction "NC_1") (pintype "passive"))
      (node (ref "IC1") (pin "10") (pinfunction "PGND_10") (pintype "passive"))
      (node (ref "IC1") (pin "18") (pinfunction "PFM/SYNC_18") (pintype "passive"))
      (node (ref "IC1") (pin "2") (pinfunction "NC_2") (pintype "passive"))
      (node (ref "IC1") (pin "22") (pinfunction "NC_22") (pintype "passive"))
      (node (ref "IC1") (pin "23") (pinfunction "NC_23") (pintype "passive"))
      (node (ref "IC1") (pin "24") (pinfunction "NC_24") (pintype "passive"))
      (node (ref "IC1") (pin "25") (pinfunction "EP_25") (pintype "passive"))
      (node (ref "IC1") (pin "7") (pinfunction "AGND_7") (pintype "passive"))
      (node (ref "Q3") (pin "S") (pinfunction "Source_S") (pintype "passive"))
      (node (ref "Q4") (pin "S") (pinfunction "Source_S") (pintype "passive"))
      (node (ref "R11") (pin "1") (pinfunction "1_1") (pintype "passive"))
      (node (ref "R12") (pin "1") (pinfunction "1_1") (pintype "passive"))
      (node (ref "RUV2") (pin "1") (pinfunction "1_1") (pintype "passive"))
      (node (ref "R_RP") (pin "1") (pinfunction "1_1") (pintype "passive"))
      (node (ref "TVS1") (pin "2") (pinfunction "Anode_2") (pintype "passive"))
    )
    (net (code "18") (name "Net-(C30-Pad2)") (class "Default")
      (node (ref "C30") (pin "2") (pinfunction "2_2") (pintype "passive"))
      (node (ref "R6") (pin "1") (pinfunction "1_1") (pintype "passive"))
    )
    (net (code "19") (name "Net-(CN1-2_1)") (class "Default")
      (node (ref "CN1") (pin "3") (pinfunction "2_1_3") (pintype "passive"))
      (node (ref "CN1") (pin "4") (pinfunction "2_2_4") (pintype "passive"))
      (node (ref "Q_RP") (pin "D") (pinfunction "D_D") (pintype "passive"))
      (node (ref "TVS1") (pin "1") (pinfunction "Cathode_1") (pintype "passive"))
    )
    (net (code "20") (name "Net-(CSN-Pad2)") (class "Default")
      (node (ref "CSN") (pin "2") (pinfunction "2_2") (pintype "passive"))
      (node (ref "RSN") (pin "1") (pinfunction "1_1") (pintype "passive"))
    )
    (net (code "21") (name "Net-(IC1-CBOOT)") (class "Default")
      (node (ref "C15") (pin "2") (pinfunction "2_2") (pintype "passive"))
      (node (ref "IC1") (pin "15") (pinfunction "CBOOT_15") (pintype "passive"))
      (node (ref "SD1") (pin "2") (pinfunction "Cathode_2") (pintype "passive"))
    )
    (net (code "22") (name "Net-(IC1-PG{slash}SYNCOUT)") (class "Default")
      (node (ref "IC1") (pin "17") (pinfunction "PG/SYNCOUT_17") (pintype "passive"))
      (node (ref "R9") (pin "1") (pinfunction "1_1") (pintype "passive"))
    )
    (net (code "23") (name "Net-(Q1-Gate)") (class "Default")
      (node (ref "Q1") (pin "G") (pinfunction "Gate_G") (pintype "passive"))
      (node (ref "RQ1") (pin "2") (pinfunction "2_2") (pintype "passive"))
    )
    (net (code "24") (name "Net-(Q2-Gate)") (class "Default")
      (node (ref "Q2") (pin "G") (pinfunction "Gate_G") (pintype "passive"))
      (node (ref "RQ2") (pin "2") (pinfunction "2_2") (pintype "passive"))
    )
    (net (code "25") (name "Net-(Q3-Gate)") (class "Default")
      (node (ref "Q3") (pin "G") (pinfunction "Gate_G") (pintype "passive"))
      (node (ref "RQ3") (pin "2") (pinfunction "2_2") (pintype "passive"))
    )
    (net (code "26") (name "Net-(Q4-Gate)") (class "Default")
      (node (ref "Q4") (pin "G") (pinfunction "Gate_G") (pintype "passive"))
      (node (ref "RQ4") (pin "2") (pinfunction "2_2") (pintype "passive"))
    )
    (net (code "27") (name "Net-(Q_RP-PadG)") (class "Default")
      (node (ref "Q_RP") (pin "G") (pinfunction "G_G") (pintype "passive"))
      (node (ref "R_RP") (pin "2") (pinfunction "2_2") (pintype "passive"))
      (node (ref "ZD_RP") (pin "1") (pinfunction "Anode_1") (pintype "passive"))
    )
    (net (code "28") (name "Net-(Q_RP-S1)") (class "Default")
      (node (ref "C9") (pin "2") (pinfunction "2_2") (pintype "passive"))
      (node (ref "L1") (pin "1") (pinfunction "1_1") (pintype "passive"))
      (node (ref "Q_RP") (pin "S") (pinfunction "S1_S") (pintype "passive"))
      (node (ref "TP1") (pin "1") (pinfunction "1_1") (pintype "passive"))
      (node (ref "ZD_RP") (pin "3") (pinfunction "Cathode_3") (pintype "passive"))
    )
    (net (code "29") (name "unconnected-(MH1-Pad1)") (class "Default")
      (node (ref "MH1") (pin "1") (pinfunction "1_1") (pintype "passive+no_connect"))
    )
    (net (code "30") (name "unconnected-(MH2-Pad1)") (class "Default")
      (node (ref "MH2") (pin "1") (pinfunction "1_1") (pintype "passive+no_connect"))
    )
    (net (code "31") (name "unconnected-(MH3-Pad1)") (class "Default")
      (node (ref "MH3") (pin "1") (pinfunction "1_1") (pintype "passive+no_connect"))
    )
    (net (code "32") (name "unconnected-(MH4-Pad1)") (class "Default")
      (node (ref "MH4") (pin "1") (pinfunction "1_1") (pintype "passive+no_connect"))
    )
    (net (code "33") (name "unconnected-(ZD_RP-Anode-Pad2)") (class "Default")
      (node (ref "ZD_RP") (pin "2") (pinfunction "Anode_2") (pintype "passive+no_connect"))
    )
  )
)
